# Digital_Testbed.net
KiCad netlist of a schematic drawn in Altium Designer
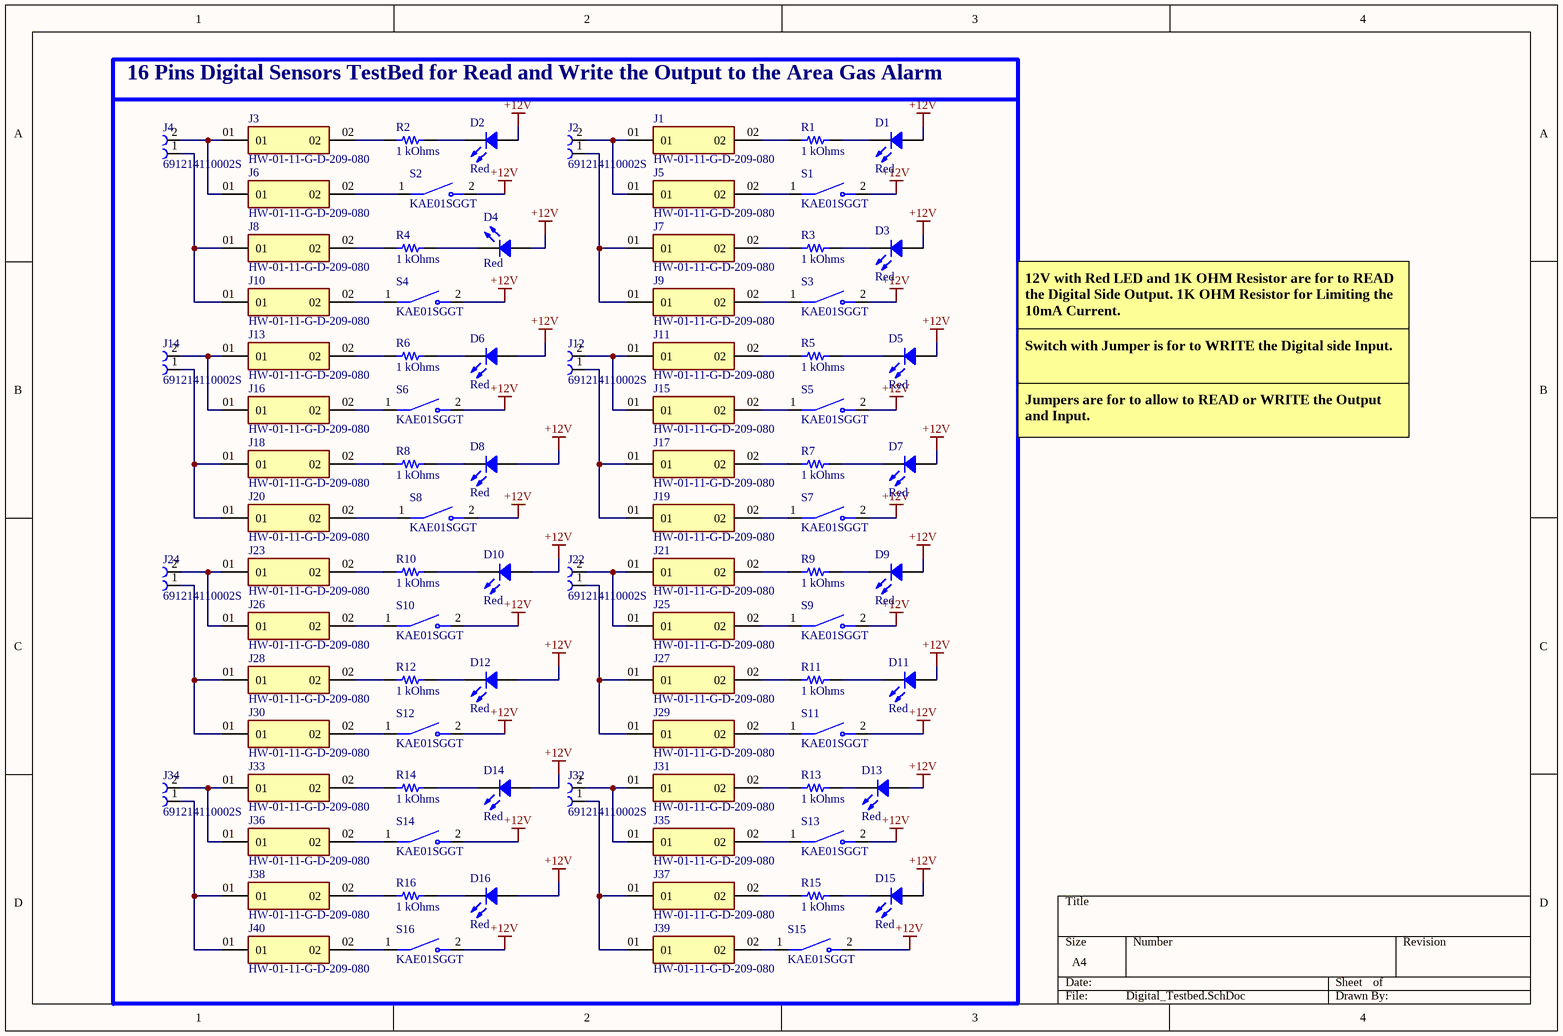
[diagram p0: Digital_Testbed.SchDoc]

(export (version "E")
  (design (tool "Eeschema 10.0.6"))
  (components
    (comp (ref "D1")
      (value "Red")
      (footprint "LED 0603_1608 RED")
      (description "LED RED CLEAR 2SMD")
      (fields
        (field (name "PART NUMBER") "19-213SDRC/S259/TR8")
        (field (name "MANUFACTURER") "Everlight Electronics Co Ltd")
      )
      (libsource (lib "Celestial Altium Library - altium_library") (part "LED"))
    )
    (comp (ref "D2")
      (value "Red")
      (footprint "LED 0603_1608 RED")
      (description "LED RED CLEAR 2SMD")
      (fields
        (field (name "PART NUMBER") "19-213SDRC/S259/TR8")
        (field (name "MANUFACTURER") "Everlight Electronics Co Ltd")
      )
      (libsource (lib "Celestial Altium Library - altium_library") (part "LED"))
    )
    (comp (ref "D3")
      (value "Red")
      (footprint "LED 0603_1608 RED")
      (description "LED RED CLEAR 2SMD")
      (fields
        (field (name "PART NUMBER") "19-213SDRC/S259/TR8")
        (field (name "MANUFACTURER") "Everlight Electronics Co Ltd")
      )
      (libsource (lib "Celestial Altium Library - altium_library") (part "LED"))
    )
    (comp (ref "D4")
      (value "Red")
      (footprint "LED 0603_1608 RED")
      (description "LED RED CLEAR 2SMD")
      (fields
        (field (name "PART NUMBER") "19-213SDRC/S259/TR8")
        (field (name "MANUFACTURER") "Everlight Electronics Co Ltd")
      )
      (libsource (lib "Celestial Altium Library - altium_library") (part "LED"))
    )
    (comp (ref "D5")
      (value "Red")
      (footprint "LED 0603_1608 RED")
      (description "LED RED CLEAR 2SMD")
      (fields
        (field (name "PART NUMBER") "19-213SDRC/S259/TR8")
        (field (name "MANUFACTURER") "Everlight Electronics Co Ltd")
      )
      (libsource (lib "Celestial Altium Library - altium_library") (part "LED"))
    )
    (comp (ref "D6")
      (value "Red")
      (footprint "LED 0603_1608 RED")
      (description "LED RED CLEAR 2SMD")
      (fields
        (field (name "PART NUMBER") "19-213SDRC/S259/TR8")
        (field (name "MANUFACTURER") "Everlight Electronics Co Ltd")
      )
      (libsource (lib "Celestial Altium Library - altium_library") (part "LED"))
    )
    (comp (ref "D7")
      (value "Red")
      (footprint "LED 0603_1608 RED")
      (description "LED RED CLEAR 2SMD")
      (fields
        (field (name "PART NUMBER") "19-213SDRC/S259/TR8")
        (field (name "MANUFACTURER") "Everlight Electronics Co Ltd")
      )
      (libsource (lib "Celestial Altium Library - altium_library") (part "LED"))
    )
    (comp (ref "D8")
      (value "Red")
      (footprint "LED 0603_1608 RED")
      (description "LED RED CLEAR 2SMD")
      (fields
        (field (name "PART NUMBER") "19-213SDRC/S259/TR8")
        (field (name "MANUFACTURER") "Everlight Electronics Co Ltd")
      )
      (libsource (lib "Celestial Altium Library - altium_library") (part "LED"))
    )
    (comp (ref "D9")
      (value "Red")
      (footprint "LED 0603_1608 RED")
      (description "LED RED CLEAR 2SMD")
      (fields
        (field (name "PART NUMBER") "19-213SDRC/S259/TR8")
        (field (name "MANUFACTURER") "Everlight Electronics Co Ltd")
      )
      (libsource (lib "Celestial Altium Library - altium_library") (part "LED"))
    )
    (comp (ref "D10")
      (value "Red")
      (footprint "LED 0603_1608 RED")
      (description "LED RED CLEAR 2SMD")
      (fields
        (field (name "PART NUMBER") "19-213SDRC/S259/TR8")
        (field (name "MANUFACTURER") "Everlight Electronics Co Ltd")
      )
      (libsource (lib "Celestial Altium Library - altium_library") (part "LED"))
    )
    (comp (ref "D11")
      (value "Red")
      (footprint "LED 0603_1608 RED")
      (description "LED RED CLEAR 2SMD")
      (fields
        (field (name "PART NUMBER") "19-213SDRC/S259/TR8")
        (field (name "MANUFACTURER") "Everlight Electronics Co Ltd")
      )
      (libsource (lib "Celestial Altium Library - altium_library") (part "LED"))
    )
    (comp (ref "D12")
      (value "Red")
      (footprint "LED 0603_1608 RED")
      (description "LED RED CLEAR 2SMD")
      (fields
        (field (name "PART NUMBER") "19-213SDRC/S259/TR8")
        (field (name "MANUFACTURER") "Everlight Electronics Co Ltd")
      )
      (libsource (lib "Celestial Altium Library - altium_library") (part "LED"))
    )
    (comp (ref "D13")
      (value "Red")
      (footprint "LED 0603_1608 RED")
      (description "LED RED CLEAR 2SMD")
      (fields
        (field (name "PART NUMBER") "19-213SDRC/S259/TR8")
        (field (name "MANUFACTURER") "Everlight Electronics Co Ltd")
      )
      (libsource (lib "Celestial Altium Library - altium_library") (part "LED"))
    )
    (comp (ref "D14")
      (value "Red")
      (footprint "LED 0603_1608 RED")
      (description "LED RED CLEAR 2SMD")
      (fields
        (field (name "PART NUMBER") "19-213SDRC/S259/TR8")
        (field (name "MANUFACTURER") "Everlight Electronics Co Ltd")
      )
      (libsource (lib "Celestial Altium Library - altium_library") (part "LED"))
    )
    (comp (ref "D15")
      (value "Red")
      (footprint "LED 0603_1608 RED")
      (description "LED RED CLEAR 2SMD")
      (fields
        (field (name "PART NUMBER") "19-213SDRC/S259/TR8")
        (field (name "MANUFACTURER") "Everlight Electronics Co Ltd")
      )
      (libsource (lib "Celestial Altium Library - altium_library") (part "LED"))
    )
    (comp (ref "D16")
      (value "Red")
      (footprint "LED 0603_1608 RED")
      (description "LED RED CLEAR 2SMD")
      (fields
        (field (name "PART NUMBER") "19-213SDRC/S259/TR8")
        (field (name "MANUFACTURER") "Everlight Electronics Co Ltd")
      )
      (libsource (lib "Celestial Altium Library - altium_library") (part "LED"))
    )
    (comp (ref "J1")
      (value "HW-01-11-G-D-209-080")
      (footprint "SAMTEC_HW-01-11-G-D-209-080")
      (description "CONN HDR 2POS STACK T/H")
      (fields (field (name "MF") "Samtec"))
      (libsource (lib "Schlib1") (part "HW-01-11-G-D-209-080"))
    )
    (comp (ref "J2")
      (value "691214110002S")
      (footprint "691214110002S")
      (description "2 Position Wire to Board Terminal Block Horizontal with Board 0.138 (3.50mm) Through Hole")
      (fields (field (name "MF") "WÃ¼rth Elektronik"))
      (libsource (lib "Schlib1") (part "691214110002S"))
    )
    (comp (ref "J3")
      (value "HW-01-11-G-D-209-080")
      (footprint "SAMTEC_HW-01-11-G-D-209-080")
      (description "CONN HDR 2POS STACK T/H")
      (fields (field (name "MF") "Samtec"))
      (libsource (lib "Schlib1") (part "HW-01-11-G-D-209-080"))
    )
    (comp (ref "J4")
      (value "691214110002S")
      (footprint "691214110002S")
      (description "2 Position Wire to Board Terminal Block Horizontal with Board 0.138 (3.50mm) Through Hole")
      (fields (field (name "MF") "WÃ¼rth Elektronik"))
      (libsource (lib "Schlib1") (part "691214110002S"))
    )
    (comp (ref "J5")
      (value "HW-01-11-G-D-209-080")
      (footprint "SAMTEC_HW-01-11-G-D-209-080")
      (description "CONN HDR 2POS STACK T/H")
      (fields (field (name "MF") "Samtec"))
      (libsource (lib "Schlib1") (part "HW-01-11-G-D-209-080"))
    )
    (comp (ref "J6")
      (value "HW-01-11-G-D-209-080")
      (footprint "SAMTEC_HW-01-11-G-D-209-080")
      (description "CONN HDR 2POS STACK T/H")
      (fields (field (name "MF") "Samtec"))
      (libsource (lib "Schlib1") (part "HW-01-11-G-D-209-080"))
    )
    (comp (ref "J7")
      (value "HW-01-11-G-D-209-080")
      (footprint "SAMTEC_HW-01-11-G-D-209-080")
      (description "CONN HDR 2POS STACK T/H")
      (fields (field (name "MF") "Samtec"))
      (libsource (lib "Schlib1") (part "HW-01-11-G-D-209-080"))
    )
    (comp (ref "J8")
      (value "HW-01-11-G-D-209-080")
      (footprint "SAMTEC_HW-01-11-G-D-209-080")
      (description "CONN HDR 2POS STACK T/H")
      (fields (field (name "MF") "Samtec"))
      (libsource (lib "Schlib1") (part "HW-01-11-G-D-209-080"))
    )
    (comp (ref "J9")
      (value "HW-01-11-G-D-209-080")
      (footprint "SAMTEC_HW-01-11-G-D-209-080")
      (description "CONN HDR 2POS STACK T/H")
      (fields (field (name "MF") "Samtec"))
      (libsource (lib "Schlib1") (part "HW-01-11-G-D-209-080"))
    )
    (comp (ref "J10")
      (value "HW-01-11-G-D-209-080")
      (footprint "SAMTEC_HW-01-11-G-D-209-080")
      (description "CONN HDR 2POS STACK T/H")
      (fields (field (name "MF") "Samtec"))
      (libsource (lib "Schlib1") (part "HW-01-11-G-D-209-080"))
    )
    (comp (ref "J11")
      (value "HW-01-11-G-D-209-080")
      (footprint "SAMTEC_HW-01-11-G-D-209-080")
      (description "CONN HDR 2POS STACK T/H")
      (fields (field (name "MF") "Samtec"))
      (libsource (lib "Schlib1") (part "HW-01-11-G-D-209-080"))
    )
    (comp (ref "J12")
      (value "691214110002S")
      (footprint "691214110002S")
      (description "2 Position Wire to Board Terminal Block Horizontal with Board 0.138 (3.50mm) Through Hole")
      (fields (field (name "MF") "WÃ¼rth Elektronik"))
      (libsource (lib "Schlib1") (part "691214110002S"))
    )
    (comp (ref "J13")
      (value "HW-01-11-G-D-209-080")
      (footprint "SAMTEC_HW-01-11-G-D-209-080")
      (description "CONN HDR 2POS STACK T/H")
      (fields (field (name "MF") "Samtec"))
      (libsource (lib "Schlib1") (part "HW-01-11-G-D-209-080"))
    )
    (comp (ref "J14")
      (value "691214110002S")
      (footprint "691214110002S")
      (description "2 Position Wire to Board Terminal Block Horizontal with Board 0.138 (3.50mm) Through Hole")
      (fields (field (name "MF") "WÃ¼rth Elektronik"))
      (libsource (lib "Schlib1") (part "691214110002S"))
    )
    (comp (ref "J15")
      (value "HW-01-11-G-D-209-080")
      (footprint "SAMTEC_HW-01-11-G-D-209-080")
      (description "CONN HDR 2POS STACK T/H")
      (fields (field (name "MF") "Samtec"))
      (libsource (lib "Schlib1") (part "HW-01-11-G-D-209-080"))
    )
    (comp (ref "J16")
      (value "HW-01-11-G-D-209-080")
      (footprint "SAMTEC_HW-01-11-G-D-209-080")
      (description "CONN HDR 2POS STACK T/H")
      (fields (field (name "MF") "Samtec"))
      (libsource (lib "Schlib1") (part "HW-01-11-G-D-209-080"))
    )
    (comp (ref "J17")
      (value "HW-01-11-G-D-209-080")
      (footprint "SAMTEC_HW-01-11-G-D-209-080")
      (description "CONN HDR 2POS STACK T/H")
      (fields (field (name "MF") "Samtec"))
      (libsource (lib "Schlib1") (part "HW-01-11-G-D-209-080"))
    )
    (comp (ref "J18")
      (value "HW-01-11-G-D-209-080")
      (footprint "SAMTEC_HW-01-11-G-D-209-080")
      (description "CONN HDR 2POS STACK T/H")
      (fields (field (name "MF") "Samtec"))
      (libsource (lib "Schlib1") (part "HW-01-11-G-D-209-080"))
    )
    (comp (ref "J19")
      (value "HW-01-11-G-D-209-080")
      (footprint "SAMTEC_HW-01-11-G-D-209-080")
      (description "CONN HDR 2POS STACK T/H")
      (fields (field (name "MF") "Samtec"))
      (libsource (lib "Schlib1") (part "HW-01-11-G-D-209-080"))
    )
    (comp (ref "J20")
      (value "HW-01-11-G-D-209-080")
      (footprint "SAMTEC_HW-01-11-G-D-209-080")
      (description "CONN HDR 2POS STACK T/H")
      (fields (field (name "MF") "Samtec"))
      (libsource (lib "Schlib1") (part "HW-01-11-G-D-209-080"))
    )
    (comp (ref "J21")
      (value "HW-01-11-G-D-209-080")
      (footprint "SAMTEC_HW-01-11-G-D-209-080")
      (description "CONN HDR 2POS STACK T/H")
      (fields (field (name "MF") "Samtec"))
      (libsource (lib "Schlib1") (part "HW-01-11-G-D-209-080"))
    )
    (comp (ref "J22")
      (value "691214110002S")
      (footprint "691214110002S")
      (description "2 Position Wire to Board Terminal Block Horizontal with Board 0.138 (3.50mm) Through Hole")
      (fields (field (name "MF") "WÃ¼rth Elektronik"))
      (libsource (lib "Schlib1") (part "691214110002S"))
    )
    (comp (ref "J23")
      (value "HW-01-11-G-D-209-080")
      (footprint "SAMTEC_HW-01-11-G-D-209-080")
      (description "CONN HDR 2POS STACK T/H")
      (fields (field (name "MF") "Samtec"))
      (libsource (lib "Schlib1") (part "HW-01-11-G-D-209-080"))
    )
    (comp (ref "J24")
      (value "691214110002S")
      (footprint "691214110002S")
      (description "2 Position Wire to Board Terminal Block Horizontal with Board 0.138 (3.50mm) Through Hole")
      (fields (field (name "MF") "WÃ¼rth Elektronik"))
      (libsource (lib "Schlib1") (part "691214110002S"))
    )
    (comp (ref "J25")
      (value "HW-01-11-G-D-209-080")
      (footprint "SAMTEC_HW-01-11-G-D-209-080")
      (description "CONN HDR 2POS STACK T/H")
      (fields (field (name "MF") "Samtec"))
      (libsource (lib "Schlib1") (part "HW-01-11-G-D-209-080"))
    )
    (comp (ref "J26")
      (value "HW-01-11-G-D-209-080")
      (footprint "SAMTEC_HW-01-11-G-D-209-080")
      (description "CONN HDR 2POS STACK T/H")
      (fields (field (name "MF") "Samtec"))
      (libsource (lib "Schlib1") (part "HW-01-11-G-D-209-080"))
    )
    (comp (ref "J27")
      (value "HW-01-11-G-D-209-080")
      (footprint "SAMTEC_HW-01-11-G-D-209-080")
      (description "CONN HDR 2POS STACK T/H")
      (fields (field (name "MF") "Samtec"))
      (libsource (lib "Schlib1") (part "HW-01-11-G-D-209-080"))
    )
    (comp (ref "J28")
      (value "HW-01-11-G-D-209-080")
      (footprint "SAMTEC_HW-01-11-G-D-209-080")
      (description "CONN HDR 2POS STACK T/H")
      (fields (field (name "MF") "Samtec"))
      (libsource (lib "Schlib1") (part "HW-01-11-G-D-209-080"))
    )
    (comp (ref "J29")
      (value "HW-01-11-G-D-209-080")
      (footprint "SAMTEC_HW-01-11-G-D-209-080")
      (description "CONN HDR 2POS STACK T/H")
      (fields (field (name "MF") "Samtec"))
      (libsource (lib "Schlib1") (part "HW-01-11-G-D-209-080"))
    )
    (comp (ref "J30")
      (value "HW-01-11-G-D-209-080")
      (footprint "SAMTEC_HW-01-11-G-D-209-080")
      (description "CONN HDR 2POS STACK T/H")
      (fields (field (name "MF") "Samtec"))
      (libsource (lib "Schlib1") (part "HW-01-11-G-D-209-080"))
    )
    (comp (ref "J31")
      (value "HW-01-11-G-D-209-080")
      (footprint "SAMTEC_HW-01-11-G-D-209-080")
      (description "CONN HDR 2POS STACK T/H")
      (fields (field (name "MF") "Samtec"))
      (libsource (lib "Schlib1") (part "HW-01-11-G-D-209-080"))
    )
    (comp (ref "J32")
      (value "691214110002S")
      (footprint "691214110002S")
      (description "2 Position Wire to Board Terminal Block Horizontal with Board 0.138 (3.50mm) Through Hole")
      (fields (field (name "MF") "WÃ¼rth Elektronik"))
      (libsource (lib "Schlib1") (part "691214110002S"))
    )
    (comp (ref "J33")
      (value "HW-01-11-G-D-209-080")
      (footprint "SAMTEC_HW-01-11-G-D-209-080")
      (description "CONN HDR 2POS STACK T/H")
      (fields (field (name "MF") "Samtec"))
      (libsource (lib "Schlib1") (part "HW-01-11-G-D-209-080"))
    )
    (comp (ref "J34")
      (value "691214110002S")
      (footprint "691214110002S")
      (description "2 Position Wire to Board Terminal Block Horizontal with Board 0.138 (3.50mm) Through Hole")
      (fields (field (name "MF") "WÃ¼rth Elektronik"))
      (libsource (lib "Schlib1") (part "691214110002S"))
    )
    (comp (ref "J35")
      (value "HW-01-11-G-D-209-080")
      (footprint "SAMTEC_HW-01-11-G-D-209-080")
      (description "CONN HDR 2POS STACK T/H")
      (fields (field (name "MF") "Samtec"))
      (libsource (lib "Schlib1") (part "HW-01-11-G-D-209-080"))
    )
    (comp (ref "J36")
      (value "HW-01-11-G-D-209-080")
      (footprint "SAMTEC_HW-01-11-G-D-209-080")
      (description "CONN HDR 2POS STACK T/H")
      (fields (field (name "MF") "Samtec"))
      (libsource (lib "Schlib1") (part "HW-01-11-G-D-209-080"))
    )
    (comp (ref "J37")
      (value "HW-01-11-G-D-209-080")
      (footprint "SAMTEC_HW-01-11-G-D-209-080")
      (description "CONN HDR 2POS STACK T/H")
      (fields (field (name "MF") "Samtec"))
      (libsource (lib "Schlib1") (part "HW-01-11-G-D-209-080"))
    )
    (comp (ref "J38")
      (value "HW-01-11-G-D-209-080")
      (footprint "SAMTEC_HW-01-11-G-D-209-080")
      (description "CONN HDR 2POS STACK T/H")
      (fields (field (name "MF") "Samtec"))
      (libsource (lib "Schlib1") (part "HW-01-11-G-D-209-080"))
    )
    (comp (ref "J39")
      (value "HW-01-11-G-D-209-080")
      (footprint "SAMTEC_HW-01-11-G-D-209-080")
      (description "CONN HDR 2POS STACK T/H")
      (fields (field (name "MF") "Samtec"))
      (libsource (lib "Schlib1") (part "HW-01-11-G-D-209-080"))
    )
    (comp (ref "J40")
      (value "HW-01-11-G-D-209-080")
      (footprint "SAMTEC_HW-01-11-G-D-209-080")
      (description "CONN HDR 2POS STACK T/H")
      (fields (field (name "MF") "Samtec"))
      (libsource (lib "Schlib1") (part "HW-01-11-G-D-209-080"))
    )
    (comp (ref "R1")
      (value "1 kOhms")
      (footprint "RES 0603_1608")
      (description "RES SMD 1K OHM 0.1% 1/16W 0603")
      (fields
        (field (name "PART NUMBER") "CPF0603B1K0E")
        (field (name "MANUFACTURER") "TE Connectivity Passive Product")
      )
      (libsource (lib "Celestial Altium Library - altium_library") (part "Resistor"))
    )
    (comp (ref "R2")
      (value "1 kOhms")
      (footprint "RES 0603_1608")
      (description "RES SMD 1K OHM 0.1% 1/16W 0603")
      (fields
        (field (name "PART NUMBER") "CPF0603B1K0E")
        (field (name "MANUFACTURER") "TE Connectivity Passive Product")
      )
      (libsource (lib "Celestial Altium Library - altium_library") (part "Resistor"))
    )
    (comp (ref "R3")
      (value "1 kOhms")
      (footprint "RES 0603_1608")
      (description "RES SMD 1K OHM 0.1% 1/16W 0603")
      (fields
        (field (name "PART NUMBER") "CPF0603B1K0E")
        (field (name "MANUFACTURER") "TE Connectivity Passive Product")
      )
      (libsource (lib "Celestial Altium Library - altium_library") (part "Resistor"))
    )
    (comp (ref "R4")
      (value "1 kOhms")
      (footprint "RES 0603_1608")
      (description "RES SMD 1K OHM 0.1% 1/16W 0603")
      (fields
        (field (name "PART NUMBER") "CPF0603B1K0E")
        (field (name "MANUFACTURER") "TE Connectivity Passive Product")
      )
      (libsource (lib "Celestial Altium Library - altium_library") (part "Resistor"))
    )
    (comp (ref "R5")
      (value "1 kOhms")
      (footprint "RES 0603_1608")
      (description "RES SMD 1K OHM 0.1% 1/16W 0603")
      (fields
        (field (name "PART NUMBER") "CPF0603B1K0E")
        (field (name "MANUFACTURER") "TE Connectivity Passive Product")
      )
      (libsource (lib "Celestial Altium Library - altium_library") (part "Resistor"))
    )
    (comp (ref "R6")
      (value "1 kOhms")
      (footprint "RES 0603_1608")
      (description "RES SMD 1K OHM 0.1% 1/16W 0603")
      (fields
        (field (name "PART NUMBER") "CPF0603B1K0E")
        (field (name "MANUFACTURER") "TE Connectivity Passive Product")
      )
      (libsource (lib "Celestial Altium Library - altium_library") (part "Resistor"))
    )
    (comp (ref "R7")
      (value "1 kOhms")
      (footprint "RES 0603_1608")
      (description "RES SMD 1K OHM 0.1% 1/16W 0603")
      (fields
        (field (name "PART NUMBER") "CPF0603B1K0E")
        (field (name "MANUFACTURER") "TE Connectivity Passive Product")
      )
      (libsource (lib "Celestial Altium Library - altium_library") (part "Resistor"))
    )
    (comp (ref "R8")
      (value "1 kOhms")
      (footprint "RES 0603_1608")
      (description "RES SMD 1K OHM 0.1% 1/16W 0603")
      (fields
        (field (name "PART NUMBER") "CPF0603B1K0E")
        (field (name "MANUFACTURER") "TE Connectivity Passive Product")
      )
      (libsource (lib "Celestial Altium Library - altium_library") (part "Resistor"))
    )
    (comp (ref "R9")
      (value "1 kOhms")
      (footprint "RES 0603_1608")
      (description "RES SMD 1K OHM 0.1% 1/16W 0603")
      (fields
        (field (name "PART NUMBER") "CPF0603B1K0E")
        (field (name "MANUFACTURER") "TE Connectivity Passive Product")
      )
      (libsource (lib "Celestial Altium Library - altium_library") (part "Resistor"))
    )
    (comp (ref "R10")
      (value "1 kOhms")
      (footprint "RES 0603_1608")
      (description "RES SMD 1K OHM 0.1% 1/16W 0603")
      (fields
        (field (name "PART NUMBER") "CPF0603B1K0E")
        (field (name "MANUFACTURER") "TE Connectivity Passive Product")
      )
      (libsource (lib "Celestial Altium Library - altium_library") (part "Resistor"))
    )
    (comp (ref "R11")
      (value "1 kOhms")
      (footprint "RES 0603_1608")
      (description "RES SMD 1K OHM 0.1% 1/16W 0603")
      (fields
        (field (name "PART NUMBER") "CPF0603B1K0E")
        (field (name "MANUFACTURER") "TE Connectivity Passive Product")
      )
      (libsource (lib "Celestial Altium Library - altium_library") (part "Resistor"))
    )
    (comp (ref "R12")
      (value "1 kOhms")
      (footprint "RES 0603_1608")
      (description "RES SMD 1K OHM 0.1% 1/16W 0603")
      (fields
        (field (name "PART NUMBER") "CPF0603B1K0E")
        (field (name "MANUFACTURER") "TE Connectivity Passive Product")
      )
      (libsource (lib "Celestial Altium Library - altium_library") (part "Resistor"))
    )
    (comp (ref "R13")
      (value "1 kOhms")
      (footprint "RES 0603_1608")
      (description "RES SMD 1K OHM 0.1% 1/16W 0603")
      (fields
        (field (name "PART NUMBER") "CPF0603B1K0E")
        (field (name "MANUFACTURER") "TE Connectivity Passive Product")
      )
      (libsource (lib "Celestial Altium Library - altium_library") (part "Resistor"))
    )
    (comp (ref "R14")
      (value "1 kOhms")
      (footprint "RES 0603_1608")
      (description "RES SMD 1K OHM 0.1% 1/16W 0603")
      (fields
        (field (name "PART NUMBER") "CPF0603B1K0E")
        (field (name "MANUFACTURER") "TE Connectivity Passive Product")
      )
      (libsource (lib "Celestial Altium Library - altium_library") (part "Resistor"))
    )
    (comp (ref "R15")
      (value "1 kOhms")
      (footprint "RES 0603_1608")
      (description "RES SMD 1K OHM 0.1% 1/16W 0603")
      (fields
        (field (name "PART NUMBER") "CPF0603B1K0E")
        (field (name "MANUFACTURER") "TE Connectivity Passive Product")
      )
      (libsource (lib "Celestial Altium Library - altium_library") (part "Resistor"))
    )
    (comp (ref "R16")
      (value "1 kOhms")
      (footprint "RES 0603_1608")
      (description "RES SMD 1K OHM 0.1% 1/16W 0603")
      (fields
        (field (name "PART NUMBER") "CPF0603B1K0E")
        (field (name "MANUFACTURER") "TE Connectivity Passive Product")
      )
      (libsource (lib "Celestial Altium Library - altium_library") (part "Resistor"))
    )
    (comp (ref "S1")
      (value "KAE01SGGT")
      (footprint "SW_KAE01SGGT")
      (description "Dip Switch SPST 1 Position Surface Mount Slide (Standard) Actuator 25mA 24VDC")
      (fields (field (name "MF") "E-Switch"))
      (libsource (lib "Schlib1") (part "KAE01SGGT"))
    )
    (comp (ref "S2")
      (value "KAE01SGGT")
      (footprint "SW_KAE01SGGT")
      (description "Dip Switch SPST 1 Position Surface Mount Slide (Standard) Actuator 25mA 24VDC")
      (fields (field (name "MF") "E-Switch"))
      (libsource (lib "Schlib1") (part "KAE01SGGT"))
    )
    (comp (ref "S3")
      (value "KAE01SGGT")
      (footprint "SW_KAE01SGGT")
      (description "Dip Switch SPST 1 Position Surface Mount Slide (Standard) Actuator 25mA 24VDC")
      (fields (field (name "MF") "E-Switch"))
      (libsource (lib "Schlib1") (part "KAE01SGGT"))
    )
    (comp (ref "S4")
      (value "KAE01SGGT")
      (footprint "SW_KAE01SGGT")
      (description "Dip Switch SPST 1 Position Surface Mount Slide (Standard) Actuator 25mA 24VDC")
      (fields (field (name "MF") "E-Switch"))
      (libsource (lib "Schlib1") (part "KAE01SGGT"))
    )
    (comp (ref "S5")
      (value "KAE01SGGT")
      (footprint "SW_KAE01SGGT")
      (description "Dip Switch SPST 1 Position Surface Mount Slide (Standard) Actuator 25mA 24VDC")
      (fields (field (name "MF") "E-Switch"))
      (libsource (lib "Schlib1") (part "KAE01SGGT"))
    )
    (comp (ref "S6")
      (value "KAE01SGGT")
      (footprint "SW_KAE01SGGT")
      (description "Dip Switch SPST 1 Position Surface Mount Slide (Standard) Actuator 25mA 24VDC")
      (fields (field (name "MF") "E-Switch"))
      (libsource (lib "Schlib1") (part "KAE01SGGT"))
    )
    (comp (ref "S7")
      (value "KAE01SGGT")
      (footprint "SW_KAE01SGGT")
      (description "Dip Switch SPST 1 Position Surface Mount Slide (Standard) Actuator 25mA 24VDC")
      (fields (field (name "MF") "E-Switch"))
      (libsource (lib "Schlib1") (part "KAE01SGGT"))
    )
    (comp (ref "S8")
      (value "KAE01SGGT")
      (footprint "SW_KAE01SGGT")
      (description "Dip Switch SPST 1 Position Surface Mount Slide (Standard) Actuator 25mA 24VDC")
      (fields (field (name "MF") "E-Switch"))
      (libsource (lib "Schlib1") (part "KAE01SGGT"))
    )
    (comp (ref "S9")
      (value "KAE01SGGT")
      (footprint "SW_KAE01SGGT")
      (description "Dip Switch SPST 1 Position Surface Mount Slide (Standard) Actuator 25mA 24VDC")
      (fields (field (name "MF") "E-Switch"))
      (libsource (lib "Schlib1") (part "KAE01SGGT"))
    )
    (comp (ref "S10")
      (value "KAE01SGGT")
      (footprint "SW_KAE01SGGT")
      (description "Dip Switch SPST 1 Position Surface Mount Slide (Standard) Actuator 25mA 24VDC")
      (fields (field (name "MF") "E-Switch"))
      (libsource (lib "Schlib1") (part "KAE01SGGT"))
    )
    (comp (ref "S11")
      (value "KAE01SGGT")
      (footprint "SW_KAE01SGGT")
      (description "Dip Switch SPST 1 Position Surface Mount Slide (Standard) Actuator 25mA 24VDC")
      (fields (field (name "MF") "E-Switch"))
      (libsource (lib "Schlib1") (part "KAE01SGGT"))
    )
    (comp (ref "S12")
      (value "KAE01SGGT")
      (footprint "SW_KAE01SGGT")
      (description "Dip Switch SPST 1 Position Surface Mount Slide (Standard) Actuator 25mA 24VDC")
      (fields (field (name "MF") "E-Switch"))
      (libsource (lib "Schlib1") (part "KAE01SGGT"))
    )
    (comp (ref "S13")
      (value "KAE01SGGT")
      (footprint "SW_KAE01SGGT")
      (description "Dip Switch SPST 1 Position Surface Mount Slide (Standard) Actuator 25mA 24VDC")
      (fields (field (name "MF") "E-Switch"))
      (libsource (lib "Schlib1") (part "KAE01SGGT"))
    )
    (comp (ref "S14")
      (value "KAE01SGGT")
      (footprint "SW_KAE01SGGT")
      (description "Dip Switch SPST 1 Position Surface Mount Slide (Standard) Actuator 25mA 24VDC")
      (fields (field (name "MF") "E-Switch"))
      (libsource (lib "Schlib1") (part "KAE01SGGT"))
    )
    (comp (ref "S15")
      (value "KAE01SGGT")
      (footprint "SW_KAE01SGGT")
      (description "Dip Switch SPST 1 Position Surface Mount Slide (Standard) Actuator 25mA 24VDC")
      (fields (field (name "MF") "E-Switch"))
      (libsource (lib "Schlib1") (part "KAE01SGGT"))
    )
    (comp (ref "S16")
      (value "KAE01SGGT")
      (footprint "SW_KAE01SGGT")
      (description "Dip Switch SPST 1 Position Surface Mount Slide (Standard) Actuator 25mA 24VDC")
      (fields (field (name "MF") "E-Switch"))
      (libsource (lib "Schlib1") (part "KAE01SGGT"))
    )
  )
  (nets
    (net (code "1") (name "+12V") (class "Default")
      (node (ref "D1") (pin "1") (pinfunction "1_1") (pintype "passive"))
      (node (ref "D10") (pin "1") (pinfunction "1_1") (pintype "passive"))
      (node (ref "D11") (pin "1") (pinfunction "1_1") (pintype "passive"))
      (node (ref "D12") (pin "1") (pinfunction "1_1") (pintype "passive"))
      (node (ref "D13") (pin "1") (pinfunction "1_1") (pintype "passive"))
      (node (ref "D14") (pin "1") (pinfunction "1_1") (pintype "passive"))
      (node (ref "D15") (pin "1") (pinfunction "1_1") (pintype "passive"))
      (node (ref "D16") (pin "1") (pinfunction "1_1") (pintype "passive"))
      (node (ref "D2") (pin "1") (pinfunction "1_1") (pintype "passive"))
      (node (ref "D3") (pin "1") (pinfunction "1_1") (pintype "passive"))
      (node (ref "D4") (pin "1") (pinfunction "1_1") (pintype "passive"))
      (node (ref "D5") (pin "1") (pinfunction "1_1") (pintype "passive"))
      (node (ref "D6") (pin "1") (pinfunction "1_1") (pintype "passive"))
      (node (ref "D7") (pin "1") (pinfunction "1_1") (pintype "passive"))
      (node (ref "D8") (pin "1") (pinfunction "1_1") (pintype "passive"))
      (node (ref "D9") (pin "1") (pinfunction "1_1") (pintype "passive"))
      (node (ref "S1") (pin "2") (pinfunction "2_2") (pintype "passive"))
      (node (ref "S10") (pin "2") (pinfunction "2_2") (pintype "passive"))
      (node (ref "S11") (pin "2") (pinfunction "2_2") (pintype "passive"))
      (node (ref "S12") (pin "2") (pinfunction "2_2") (pintype "passive"))
      (node (ref "S13") (pin "2") (pinfunction "2_2") (pintype "passive"))
      (node (ref "S14") (pin "2") (pinfunction "2_2") (pintype "passive"))
      (node (ref "S15") (pin "2") (pinfunction "2_2") (pintype "passive"))
      (node (ref "S16") (pin "2") (pinfunction "2_2") (pintype "passive"))
      (node (ref "S2") (pin "2") (pinfunction "2_2") (pintype "passive"))
      (node (ref "S3") (pin "2") (pinfunction "2_2") (pintype "passive"))
      (node (ref "S4") (pin "2") (pinfunction "2_2") (pintype "passive"))
      (node (ref "S5") (pin "2") (pinfunction "2_2") (pintype "passive"))
      (node (ref "S6") (pin "2") (pinfunction "2_2") (pintype "passive"))
      (node (ref "S7") (pin "2") (pinfunction "2_2") (pintype "passive"))
      (node (ref "S8") (pin "2") (pinfunction "2_2") (pintype "passive"))
      (node (ref "S9") (pin "2") (pinfunction "2_2") (pintype "passive"))
    )
    (net (code "2") (name "Net-(D1-Pad2)") (class "Default")
      (node (ref "D1") (pin "2") (pinfunction "2_2") (pintype "passive"))
      (node (ref "R1") (pin "2") (pinfunction "2_2") (pintype "passive"))
    )
    (net (code "3") (name "Net-(D2-Pad2)") (class "Default")
      (node (ref "D2") (pin "2") (pinfunction "2_2") (pintype "passive"))
      (node (ref "R2") (pin "2") (pinfunction "2_2") (pintype "passive"))
    )
    (net (code "4") (name "Net-(D3-Pad2)") (class "Default")
      (node (ref "D3") (pin "2") (pinfunction "2_2") (pintype "passive"))
      (node (ref "R3") (pin "2") (pinfunction "2_2") (pintype "passive"))
    )
    (net (code "5") (name "Net-(D4-Pad2)") (class "Default")
      (node (ref "D4") (pin "2") (pinfunction "2_2") (pintype "passive"))
      (node (ref "R4") (pin "2") (pinfunction "2_2") (pintype "passive"))
    )
    (net (code "6") (name "Net-(D5-Pad2)") (class "Default")
      (node (ref "D5") (pin "2") (pinfunction "2_2") (pintype "passive"))
      (node (ref "R5") (pin "2") (pinfunction "2_2") (pintype "passive"))
    )
    (net (code "7") (name "Net-(D6-Pad2)") (class "Default")
      (node (ref "D6") (pin "2") (pinfunction "2_2") (pintype "passive"))
      (node (ref "R6") (pin "2") (pinfunction "2_2") (pintype "passive"))
    )
    (net (code "8") (name "Net-(D7-Pad2)") (class "Default")
      (node (ref "D7") (pin "2") (pinfunction "2_2") (pintype "passive"))
      (node (ref "R7") (pin "2") (pinfunction "2_2") (pintype "passive"))
    )
    (net (code "9") (name "Net-(D8-Pad2)") (class "Default")
      (node (ref "D8") (pin "2") (pinfunction "2_2") (pintype "passive"))
      (node (ref "R8") (pin "2") (pinfunction "2_2") (pintype "passive"))
    )
    (net (code "10") (name "Net-(D9-Pad2)") (class "Default")
      (node (ref "D9") (pin "2") (pinfunction "2_2") (pintype "passive"))
      (node (ref "R9") (pin "2") (pinfunction "2_2") (pintype "passive"))
    )
    (net (code "11") (name "Net-(D10-Pad2)") (class "Default")
      (node (ref "D10") (pin "2") (pinfunction "2_2") (pintype "passive"))
      (node (ref "R10") (pin "2") (pinfunction "2_2") (pintype "passive"))
    )
    (net (code "12") (name "Net-(D11-Pad2)") (class "Default")
      (node (ref "D11") (pin "2") (pinfunction "2_2") (pintype "passive"))
      (node (ref "R11") (pin "2") (pinfunction "2_2") (pintype "passive"))
    )
    (net (code "13") (name "Net-(D12-Pad2)") (class "Default")
      (node (ref "D12") (pin "2") (pinfunction "2_2") (pintype "passive"))
      (node (ref "R12") (pin "2") (pinfunction "2_2") (pintype "passive"))
    )
    (net (code "14") (name "Net-(D13-Pad2)") (class "Default")
      (node (ref "D13") (pin "2") (pinfunction "2_2") (pintype "passive"))
      (node (ref "R13") (pin "2") (pinfunction "2_2") (pintype "passive"))
    )
    (net (code "15") (name "Net-(D14-Pad2)") (class "Default")
      (node (ref "D14") (pin "2") (pinfunction "2_2") (pintype "passive"))
      (node (ref "R14") (pin "2") (pinfunction "2_2") (pintype "passive"))
    )
    (net (code "16") (name "Net-(D15-Pad2)") (class "Default")
      (node (ref "D15") (pin "2") (pinfunction "2_2") (pintype "passive"))
      (node (ref "R15") (pin "2") (pinfunction "2_2") (pintype "passive"))
    )
    (net (code "17") (name "Net-(D16-Pad2)") (class "Default")
      (node (ref "D16") (pin "2") (pinfunction "2_2") (pintype "passive"))
      (node (ref "R16") (pin "2") (pinfunction "2_2") (pintype "passive"))
    )
    (net (code "18") (name "Net-(J1-Pad01)") (class "Default")
      (node (ref "J1") (pin "01") (pinfunction "01_01") (pintype "passive"))
      (node (ref "J2") (pin "2") (pinfunction "2_2") (pintype "passive"))
      (node (ref "J5") (pin "01") (pinfunction "01_01") (pintype "passive"))
    )
    (net (code "19") (name "Net-(J1-Pad02)") (class "Default")
      (node (ref "J1") (pin "02") (pinfunction "02_02") (pintype "passive"))
      (node (ref "R1") (pin "1") (pinfunction "1_1") (pintype "passive"))
    )
    (net (code "20") (name "Net-(J2-Pad1)") (class "Default")
      (node (ref "J2") (pin "1") (pinfunction "1_1") (pintype "passive"))
      (node (ref "J7") (pin "01") (pinfunction "01_01") (pintype "passive"))
      (node (ref "J9") (pin "01") (pinfunction "01_01") (pintype "passive"))
    )
    (net (code "21") (name "Net-(J3-Pad01)") (class "Default")
      (node (ref "J3") (pin "01") (pinfunction "01_01") (pintype "passive"))
      (node (ref "J4") (pin "2") (pinfunction "2_2") (pintype "passive"))
      (node (ref "J6") (pin "01") (pinfunction "01_01") (pintype "passive"))
    )
    (net (code "22") (name "Net-(J3-Pad02)") (class "Default")
      (node (ref "J3") (pin "02") (pinfunction "02_02") (pintype "passive"))
      (node (ref "R2") (pin "1") (pinfunction "1_1") (pintype "passive"))
    )
    (net (code "23") (name "Net-(J5-Pad02)") (class "Default")
      (node (ref "J5") (pin "02") (pinfunction "02_02") (pintype "passive"))
      (node (ref "S1") (pin "1") (pinfunction "1_1") (pintype "passive"))
    )
    (net (code "24") (name "Net-(J6-Pad02)") (class "Default")
      (node (ref "J6") (pin "02") (pinfunction "02_02") (pintype "passive"))
      (node (ref "S2") (pin "1") (pinfunction "1_1") (pintype "passive"))
    )
    (net (code "25") (name "Net-(J7-Pad02)") (class "Default")
      (node (ref "J7") (pin "02") (pinfunction "02_02") (pintype "passive"))
      (node (ref "R3") (pin "1") (pinfunction "1_1") (pintype "passive"))
    )
    (net (code "26") (name "Net-(J8-Pad02)") (class "Default")
      (node (ref "J8") (pin "02") (pinfunction "02_02") (pintype "passive"))
      (node (ref "R4") (pin "1") (pinfunction "1_1") (pintype "passive"))
    )
    (net (code "27") (name "Net-(J9-Pad02)") (class "Default")
      (node (ref "J9") (pin "02") (pinfunction "02_02") (pintype "passive"))
      (node (ref "S3") (pin "1") (pinfunction "1_1") (pintype "passive"))
    )
    (net (code "28") (name "Net-(J10-Pad01)") (class "Default")
      (node (ref "J10") (pin "01") (pinfunction "01_01") (pintype "passive"))
      (node (ref "J4") (pin "1") (pinfunction "1_1") (pintype "passive"))
      (node (ref "J8") (pin "01") (pinfunction "01_01") (pintype "passive"))
    )
    (net (code "29") (name "Net-(J10-Pad02)") (class "Default")
      (node (ref "J10") (pin "02") (pinfunction "02_02") (pintype "passive"))
      (node (ref "S4") (pin "1") (pinfunction "1_1") (pintype "passive"))
    )
    (net (code "30") (name "Net-(J11-Pad01)") (class "Default")
      (node (ref "J11") (pin "01") (pinfunction "01_01") (pintype "passive"))
      (node (ref "J12") (pin "2") (pinfunction "2_2") (pintype "passive"))
      (node (ref "J15") (pin "01") (pinfunction "01_01") (pintype "passive"))
    )
    (net (code "31") (name "Net-(J11-Pad02)") (class "Default")
      (node (ref "J11") (pin "02") (pinfunction "02_02") (pintype "passive"))
      (node (ref "R5") (pin "1") (pinfunction "1_1") (pintype "passive"))
    )
    (net (code "32") (name "Net-(J12-Pad1)") (class "Default")
      (node (ref "J12") (pin "1") (pinfunction "1_1") (pintype "passive"))
      (node (ref "J17") (pin "01") (pinfunction "01_01") (pintype "passive"))
      (node (ref "J19") (pin "01") (pinfunction "01_01") (pintype "passive"))
    )
    (net (code "33") (name "Net-(J13-Pad01)") (class "Default")
      (node (ref "J13") (pin "01") (pinfunction "01_01") (pintype "passive"))
      (node (ref "J14") (pin "2") (pinfunction "2_2") (pintype "passive"))
      (node (ref "J16") (pin "01") (pinfunction "01_01") (pintype "passive"))
    )
    (net (code "34") (name "Net-(J13-Pad02)") (class "Default")
      (node (ref "J13") (pin "02") (pinfunction "02_02") (pintype "passive"))
      (node (ref "R6") (pin "1") (pinfunction "1_1") (pintype "passive"))
    )
    (net (code "35") (name "Net-(J14-Pad1)") (class "Default")
      (node (ref "J14") (pin "1") (pinfunction "1_1") (pintype "passive"))
      (node (ref "J18") (pin "01") (pinfunction "01_01") (pintype "passive"))
      (node (ref "J20") (pin "01") (pinfunction "01_01") (pintype "passive"))
    )
    (net (code "36") (name "Net-(J15-Pad02)") (class "Default")
      (node (ref "J15") (pin "02") (pinfunction "02_02") (pintype "passive"))
      (node (ref "S5") (pin "1") (pinfunction "1_1") (pintype "passive"))
    )
    (net (code "37") (name "Net-(J16-Pad02)") (class "Default")
      (node (ref "J16") (pin "02") (pinfunction "02_02") (pintype "passive"))
      (node (ref "S6") (pin "1") (pinfunction "1_1") (pintype "passive"))
    )
    (net (code "38") (name "Net-(J17-Pad02)") (class "Default")
      (node (ref "J17") (pin "02") (pinfunction "02_02") (pintype "passive"))
      (node (ref "R7") (pin "1") (pinfunction "1_1") (pintype "passive"))
    )
    (net (code "39") (name "Net-(J18-Pad02)") (class "Default")
      (node (ref "J18") (pin "02") (pinfunction "02_02") (pintype "passive"))
      (node (ref "R8") (pin "1") (pinfunction "1_1") (pintype "passive"))
    )
    (net (code "40") (name "Net-(J19-Pad02)") (class "Default")
      (node (ref "J19") (pin "02") (pinfunction "02_02") (pintype "passive"))
      (node (ref "S7") (pin "1") (pinfunction "1_1") (pintype "passive"))
    )
    (net (code "41") (name "Net-(J20-Pad02)") (class "Default")
      (node (ref "J20") (pin "02") (pinfunction "02_02") (pintype "passive"))
      (node (ref "S8") (pin "1") (pinfunction "1_1") (pintype "passive"))
    )
    (net (code "42") (name "Net-(J21-Pad01)") (class "Default")
      (node (ref "J21") (pin "01") (pinfunction "01_01") (pintype "passive"))
      (node (ref "J22") (pin "2") (pinfunction "2_2") (pintype "passive"))
      (node (ref "J25") (pin "01") (pinfunction "01_01") (pintype "passive"))
    )
    (net (code "43") (name "Net-(J21-Pad02)") (class "Default")
      (node (ref "J21") (pin "02") (pinfunction "02_02") (pintype "passive"))
      (node (ref "R9") (pin "1") (pinfunction "1_1") (pintype "passive"))
    )
    (net (code "44") (name "Net-(J22-Pad1)") (class "Default")
      (node (ref "J22") (pin "1") (pinfunction "1_1") (pintype "passive"))
      (node (ref "J27") (pin "01") (pinfunction "01_01") (pintype "passive"))
      (node (ref "J29") (pin "01") (pinfunction "01_01") (pintype "passive"))
    )
    (net (code "45") (name "Net-(J23-Pad01)") (class "Default")
      (node (ref "J23") (pin "01") (pinfunction "01_01") (pintype "passive"))
      (node (ref "J24") (pin "2") (pinfunction "2_2") (pintype "passive"))
      (node (ref "J26") (pin "01") (pinfunction "01_01") (pintype "passive"))
    )
    (net (code "46") (name "Net-(J23-Pad02)") (class "Default")
      (node (ref "J23") (pin "02") (pinfunction "02_02") (pintype "passive"))
      (node (ref "R10") (pin "1") (pinfunction "1_1") (pintype "passive"))
    )
    (net (code "47") (name "Net-(J24-Pad1)") (class "Default")
      (node (ref "J24") (pin "1") (pinfunction "1_1") (pintype "passive"))
      (node (ref "J28") (pin "01") (pinfunction "01_01") (pintype "passive"))
      (node (ref "J30") (pin "01") (pinfunction "01_01") (pintype "passive"))
    )
    (net (code "48") (name "Net-(J25-Pad02)") (class "Default")
      (node (ref "J25") (pin "02") (pinfunction "02_02") (pintype "passive"))
      (node (ref "S9") (pin "1") (pinfunction "1_1") (pintype "passive"))
    )
    (net (code "49") (name "Net-(J26-Pad02)") (class "Default")
      (node (ref "J26") (pin "02") (pinfunction "02_02") (pintype "passive"))
      (node (ref "S10") (pin "1") (pinfunction "1_1") (pintype "passive"))
    )
    (net (code "50") (name "Net-(J27-Pad02)") (class "Default")
      (node (ref "J27") (pin "02") (pinfunction "02_02") (pintype "passive"))
      (node (ref "R11") (pin "1") (pinfunction "1_1") (pintype "passive"))
    )
    (net (code "51") (name "Net-(J28-Pad02)") (class "Default")
      (node (ref "J28") (pin "02") (pinfunction "02_02") (pintype "passive"))
      (node (ref "R12") (pin "1") (pinfunction "1_1") (pintype "passive"))
    )
    (net (code "52") (name "Net-(J29-Pad02)") (class "Default")
      (node (ref "J29") (pin "02") (pinfunction "02_02") (pintype "passive"))
      (node (ref "S11") (pin "1") (pinfunction "1_1") (pintype "passive"))
    )
    (net (code "53") (name "Net-(J30-Pad02)") (class "Default")
      (node (ref "J30") (pin "02") (pinfunction "02_02") (pintype "passive"))
      (node (ref "S12") (pin "1") (pinfunction "1_1") (pintype "passive"))
    )
    (net (code "54") (name "Net-(J31-Pad01)") (class "Default")
      (node (ref "J31") (pin "01") (pinfunction "01_01") (pintype "passive"))
      (node (ref "J32") (pin "2") (pinfunction "2_2") (pintype "passive"))
      (node (ref "J35") (pin "01") (pinfunction "01_01") (pintype "passive"))
    )
    (net (code "55") (name "Net-(J31-Pad02)") (class "Default")
      (node (ref "J31") (pin "02") (pinfunction "02_02") (pintype "passive"))
      (node (ref "R13") (pin "1") (pinfunction "1_1") (pintype "passive"))
    )
    (net (code "56") (name "Net-(J32-Pad1)") (class "Default")
      (node (ref "J32") (pin "1") (pinfunction "1_1") (pintype "passive"))
      (node (ref "J37") (pin "01") (pinfunction "01_01") (pintype "passive"))
      (node (ref "J39") (pin "01") (pinfunction "01_01") (pintype "passive"))
    )
    (net (code "57") (name "Net-(J33-Pad01)") (class "Default")
      (node (ref "J33") (pin "01") (pinfunction "01_01") (pintype "passive"))
      (node (ref "J34") (pin "2") (pinfunction "2_2") (pintype "passive"))
      (node (ref "J36") (pin "01") (pinfunction "01_01") (pintype "passive"))
    )
    (net (code "58") (name "Net-(J33-Pad02)") (class "Default")
      (node (ref "J33") (pin "02") (pinfunction "02_02") (pintype "passive"))
      (node (ref "R14") (pin "1") (pinfunction "1_1") (pintype "passive"))
    )
    (net (code "59") (name "Net-(J34-Pad1)") (class "Default")
      (node (ref "J34") (pin "1") (pinfunction "1_1") (pintype "passive"))
      (node (ref "J38") (pin "01") (pinfunction "01_01") (pintype "passive"))
      (node (ref "J40") (pin "01") (pinfunction "01_01") (pintype "passive"))
    )
    (net (code "60") (name "Net-(J35-Pad02)") (class "Default")
      (node (ref "J35") (pin "02") (pinfunction "02_02") (pintype "passive"))
      (node (ref "S13") (pin "1") (pinfunction "1_1") (pintype "passive"))
    )
    (net (code "61") (name "Net-(J36-Pad02)") (class "Default")
      (node (ref "J36") (pin "02") (pinfunction "02_02") (pintype "passive"))
      (node (ref "S14") (pin "1") (pinfunction "1_1") (pintype "passive"))
    )
    (net (code "62") (name "Net-(J37-Pad02)") (class "Default")
      (node (ref "J37") (pin "02") (pinfunction "02_02") (pintype "passive"))
      (node (ref "R15") (pin "1") (pinfunction "1_1") (pintype "passive"))
    )
    (net (code "63") (name "Net-(J38-Pad02)") (class "Default")
      (node (ref "J38") (pin "02") (pinfunction "02_02") (pintype "passive"))
      (node (ref "R16") (pin "1") (pinfunction "1_1") (pintype "passive"))
    )
    (net (code "64") (name "Net-(J39-Pad02)") (class "Default")
      (node (ref "J39") (pin "02") (pinfunction "02_02") (pintype "passive"))
      (node (ref "S15") (pin "1") (pinfunction "1_1") (pintype "passive"))
    )
    (net (code "65") (name "Net-(J40-Pad02)") (class "Default")
      (node (ref "J40") (pin "02") (pinfunction "02_02") (pintype "passive"))
      (node (ref "S16") (pin "1") (pinfunction "1_1") (pintype "passive"))
    )
  )
)
